# llrf_afe_fmc.net
KiCad netlist of a schematic drawn in Altium Designer
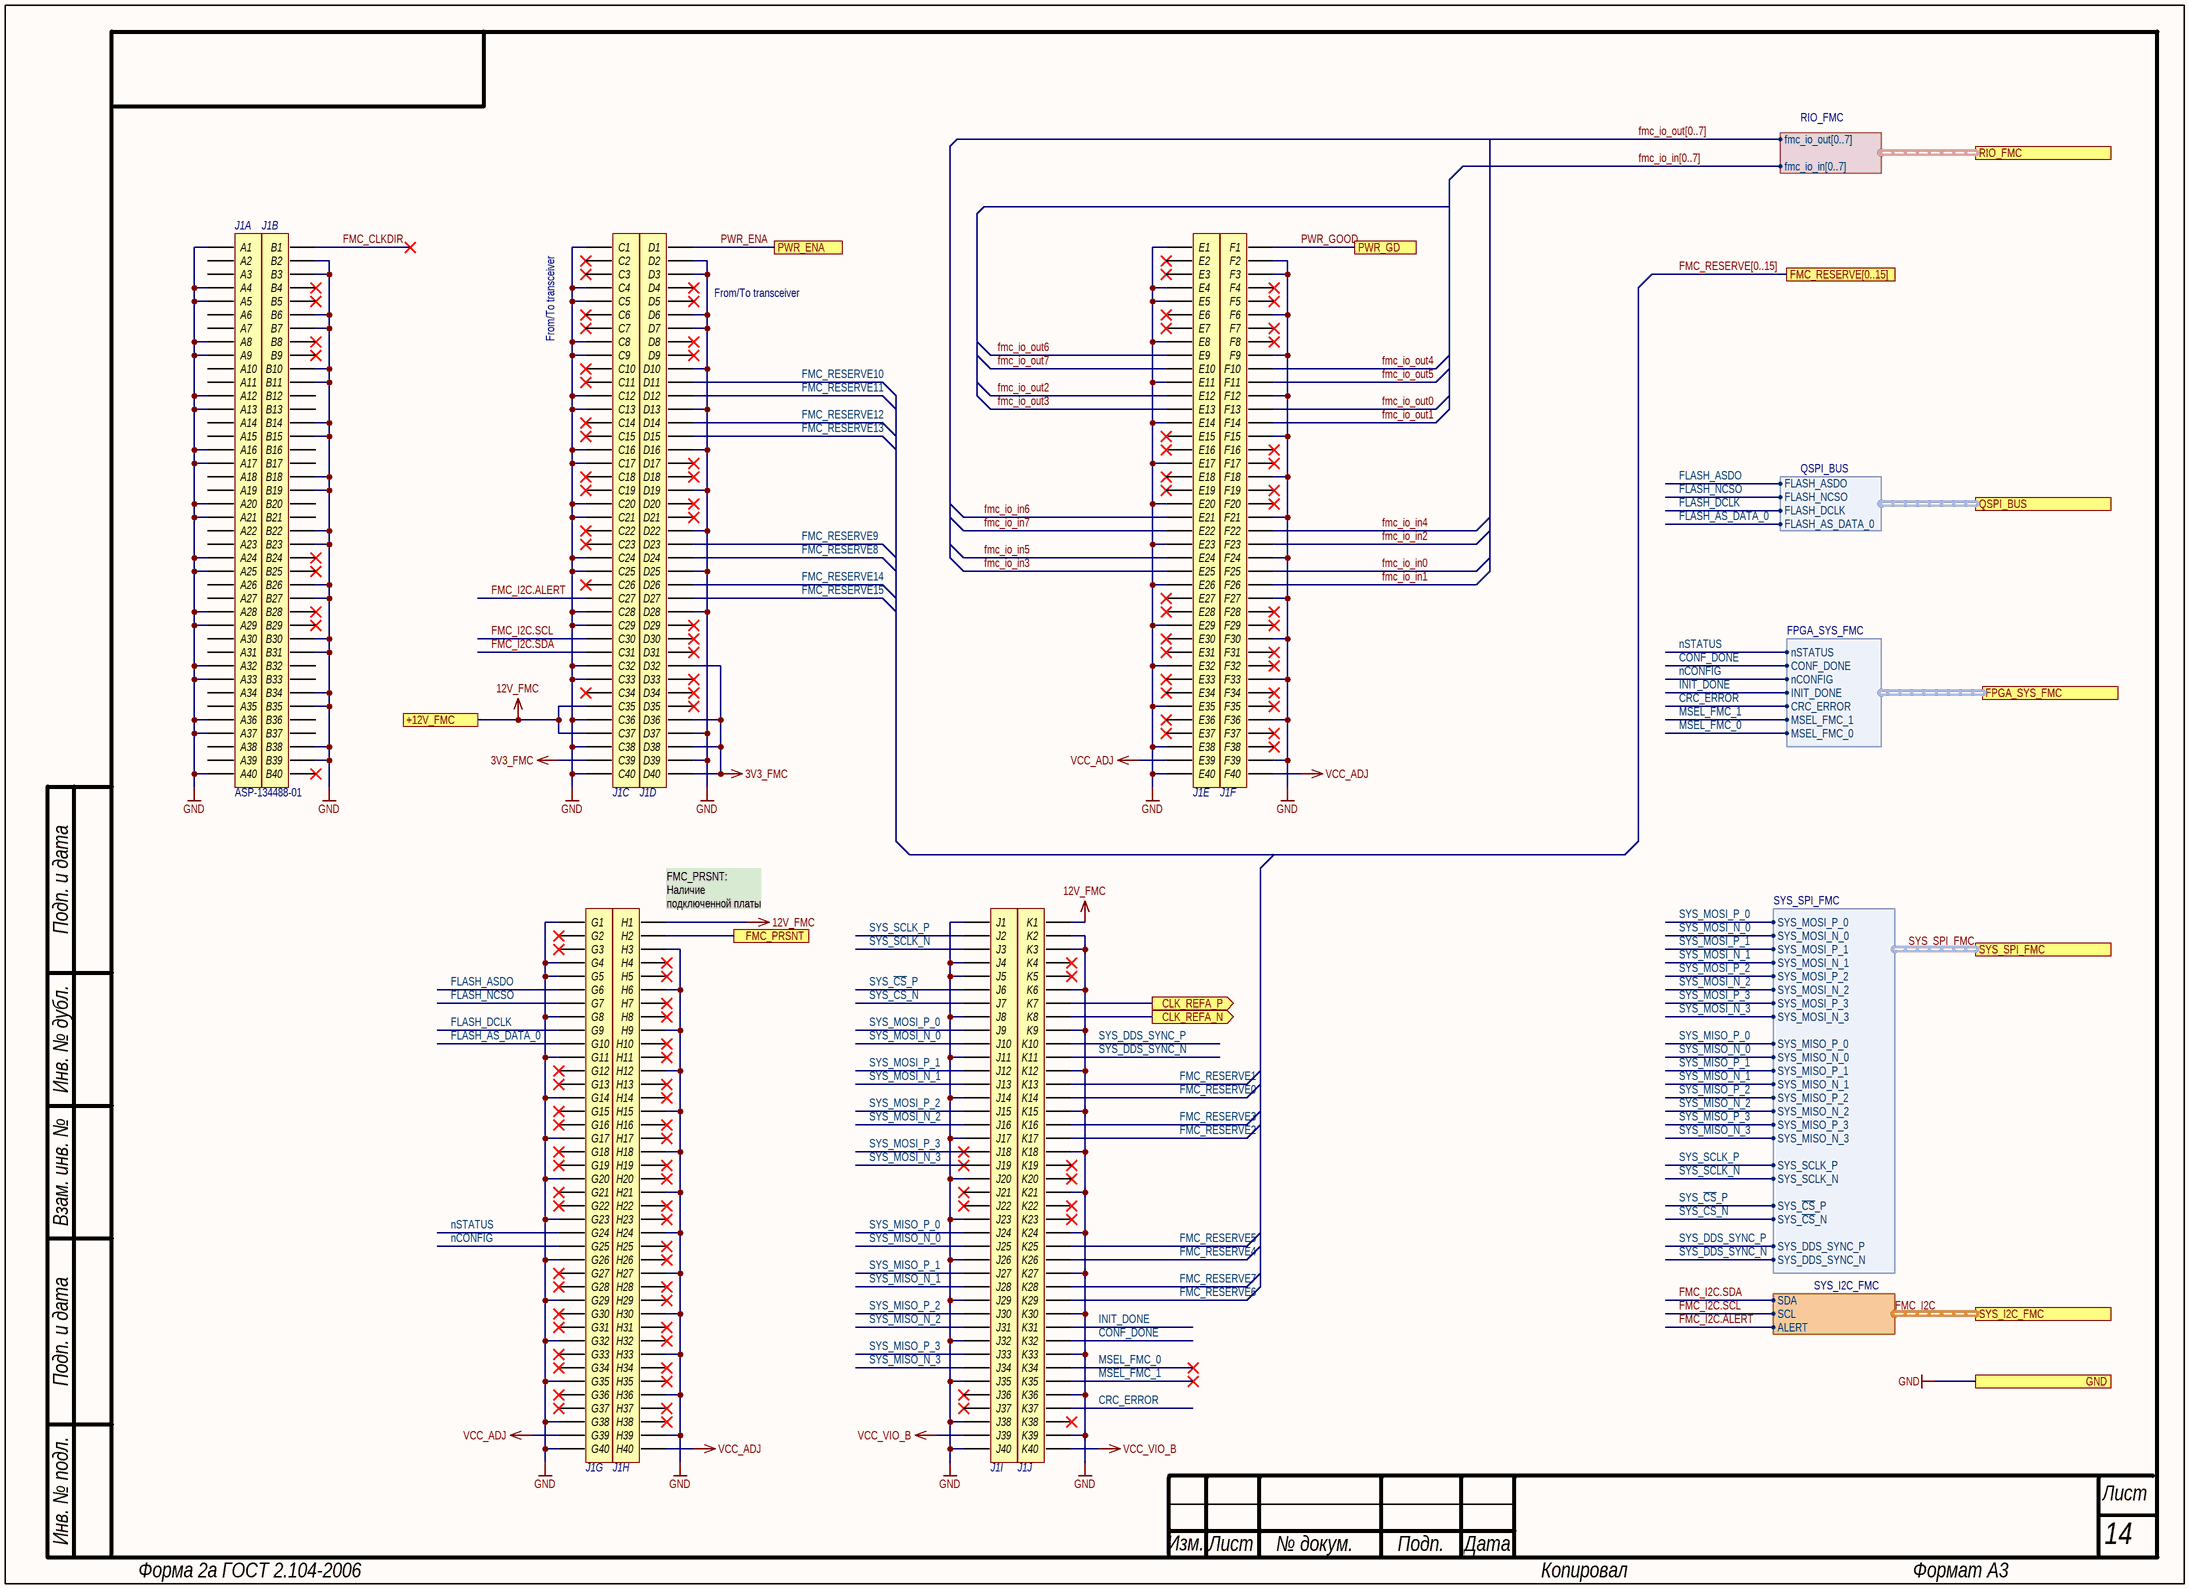
[diagram p0: llrf_afe_fmc.SchDoc]

(export (version "E")
  (design (tool "Eeschema 10.0.6"))
  (components
    (comp (ref "J1")
      (value "ASP-134488-01")
      (footprint "ASP-134488-01")
      (description "Socket Array Assembly, Surface Mount, 0.050\" Pitch, 400 Pins")
      (fields
        (field (name "MANUFACTURER") "SAMTEC")
        (field (name "НАИМЕНОВАНИЕ") "ASP-134488-01")
        (field (name "CREATED") "March 24, 2015 - Wendy Xin")
      )
      (libsource (lib "Connector") (part "ASP-134488-01"))
    )
  )
  (nets
    (net (code "6") (name "/CLK_REFA_N") (class "Default")
      (node (ref "J1") (pin "K8") (pinfunction "K8_K8") (pintype "passive"))
    )
    (net (code "7") (name "/CLK_REFA_P") (class "Default")
      (node (ref "J1") (pin "K7") (pinfunction "K7_K7") (pintype "passive"))
    )
    (net (code "8") (name "/CONF_DONE") (class "Default")
      (node (ref "J1") (pin "K32") (pinfunction "K32_K32") (pintype "passive"))
    )
    (net (code "9") (name "/CRC_ERROR") (class "Default")
      (node (ref "J1") (pin "K37") (pinfunction "K37_K37") (pintype "passive"))
    )
    (net (code "10") (name "/FLASH_ASDO") (class "Default")
      (node (ref "J1") (pin "G6") (pinfunction "G6_G6") (pintype "passive"))
    )
    (net (code "11") (name "/FLASH_AS_DATA_0") (class "Default")
      (node (ref "J1") (pin "G10") (pinfunction "G10_G10") (pintype "passive"))
    )
    (net (code "12") (name "/FLASH_DCLK") (class "Default")
      (node (ref "J1") (pin "G9") (pinfunction "G9_G9") (pintype "passive"))
    )
    (net (code "13") (name "/FLASH_NCSO") (class "Default")
      (node (ref "J1") (pin "G7") (pinfunction "G7_G7") (pintype "passive"))
    )
    (net (code "14") (name "/FMC_CLKDIR") (class "Default")
      (node (ref "J1") (pin "B1") (pinfunction "B1_B1") (pintype "passive+no_connect"))
    )
    (net (code "15") (name "/FMC_I2C.ALERT") (class "Default")
      (node (ref "J1") (pin "C27") (pinfunction "C27_C27") (pintype "passive"))
    )
    (net (code "16") (name "/FMC_I2C.SCL") (class "Default")
      (node (ref "J1") (pin "C30") (pinfunction "C30_C30") (pintype "passive"))
    )
    (net (code "17") (name "/FMC_I2C.SDA") (class "Default")
      (node (ref "J1") (pin "C31") (pinfunction "C31_C31") (pintype "passive"))
    )
    (net (code "19") (name "/FMC_PRSNT") (class "Default")
      (node (ref "J1") (pin "H2") (pinfunction "H2_H2") (pintype "passive"))
    )
    (net (code "20") (name "/FMC_RESERVE0") (class "Default")
      (node (ref "J1") (pin "K14") (pinfunction "K14_K14") (pintype "passive"))
    )
    (net (code "21") (name "/FMC_RESERVE1") (class "Default")
      (node (ref "J1") (pin "K13") (pinfunction "K13_K13") (pintype "passive"))
    )
    (net (code "22") (name "/FMC_RESERVE2") (class "Default")
      (node (ref "J1") (pin "K17") (pinfunction "K17_K17") (pintype "passive"))
    )
    (net (code "23") (name "/FMC_RESERVE3") (class "Default")
      (node (ref "J1") (pin "K16") (pinfunction "K16_K16") (pintype "passive"))
    )
    (net (code "24") (name "/FMC_RESERVE4") (class "Default")
      (node (ref "J1") (pin "K26") (pinfunction "K26_K26") (pintype "passive"))
    )
    (net (code "25") (name "/FMC_RESERVE5") (class "Default")
      (node (ref "J1") (pin "K25") (pinfunction "K25_K25") (pintype "passive"))
    )
    (net (code "26") (name "/FMC_RESERVE6") (class "Default")
      (node (ref "J1") (pin "K29") (pinfunction "K29_K29") (pintype "passive"))
    )
    (net (code "27") (name "/FMC_RESERVE7") (class "Default")
      (node (ref "J1") (pin "K28") (pinfunction "K28_K28") (pintype "passive"))
    )
    (net (code "28") (name "/FMC_RESERVE8") (class "Default")
      (node (ref "J1") (pin "D24") (pinfunction "D24_D24") (pintype "passive"))
    )
    (net (code "29") (name "/FMC_RESERVE9") (class "Default")
      (node (ref "J1") (pin "D23") (pinfunction "D23_D23") (pintype "passive"))
    )
    (net (code "30") (name "/FMC_RESERVE10") (class "Default")
      (node (ref "J1") (pin "D11") (pinfunction "D11_D11") (pintype "passive"))
    )
    (net (code "31") (name "/FMC_RESERVE11") (class "Default")
      (node (ref "J1") (pin "D12") (pinfunction "D12_D12") (pintype "passive"))
    )
    (net (code "32") (name "/FMC_RESERVE12") (class "Default")
      (node (ref "J1") (pin "D14") (pinfunction "D14_D14") (pintype "passive"))
    )
    (net (code "33") (name "/FMC_RESERVE13") (class "Default")
      (node (ref "J1") (pin "D15") (pinfunction "D15_D15") (pintype "passive"))
    )
    (net (code "34") (name "/FMC_RESERVE14") (class "Default")
      (node (ref "J1") (pin "D26") (pinfunction "D26_D26") (pintype "passive"))
    )
    (net (code "35") (name "/FMC_RESERVE15") (class "Default")
      (node (ref "J1") (pin "D27") (pinfunction "D27_D27") (pintype "passive"))
    )
    (net (code "37") (name "/INIT_DONE") (class "Default")
      (node (ref "J1") (pin "K31") (pinfunction "K31_K31") (pintype "passive"))
    )
    (net (code "38") (name "/MSEL_FMC_0") (class "Default")
      (node (ref "J1") (pin "K34") (pinfunction "K34_K34") (pintype "passive"))
    )
    (net (code "39") (name "/MSEL_FMC_1") (class "Default")
      (node (ref "J1") (pin "K35") (pinfunction "K35_K35") (pintype "passive"))
    )
    (net (code "40") (name "/PWR_ENA") (class "Default")
      (node (ref "J1") (pin "D1") (pinfunction "D1_D1") (pintype "passive"))
    )
    (net (code "41") (name "/PWR_GOOD") (class "Default")
      (node (ref "J1") (pin "F1") (pinfunction "F1_F1") (pintype "passive"))
    )
    (net (code "43") (name "/SYS_DDS_SYNC_N") (class "Default")
      (node (ref "J1") (pin "K11") (pinfunction "K11_K11") (pintype "passive"))
    )
    (net (code "44") (name "/SYS_DDS_SYNC_P") (class "Default")
      (node (ref "J1") (pin "K10") (pinfunction "K10_K10") (pintype "passive"))
    )
    (net (code "45") (name "/SYS_MISO_N_0") (class "Default")
      (node (ref "J1") (pin "J25") (pinfunction "J25_J25") (pintype "passive"))
    )
    (net (code "46") (name "/SYS_MISO_N_1") (class "Default")
      (node (ref "J1") (pin "J28") (pinfunction "J28_J28") (pintype "passive"))
    )
    (net (code "47") (name "/SYS_MISO_N_2") (class "Default")
      (node (ref "J1") (pin "J31") (pinfunction "J31_J31") (pintype "passive"))
    )
    (net (code "48") (name "/SYS_MISO_N_3") (class "Default")
      (node (ref "J1") (pin "J34") (pinfunction "J34_J34") (pintype "passive"))
    )
    (net (code "49") (name "/SYS_MISO_P_0") (class "Default")
      (node (ref "J1") (pin "J24") (pinfunction "J24_J24") (pintype "passive"))
    )
    (net (code "50") (name "/SYS_MISO_P_1") (class "Default")
      (node (ref "J1") (pin "J27") (pinfunction "J27_J27") (pintype "passive"))
    )
    (net (code "51") (name "/SYS_MISO_P_2") (class "Default")
      (node (ref "J1") (pin "J30") (pinfunction "J30_J30") (pintype "passive"))
    )
    (net (code "52") (name "/SYS_MISO_P_3") (class "Default")
      (node (ref "J1") (pin "J33") (pinfunction "J33_J33") (pintype "passive"))
    )
    (net (code "53") (name "/SYS_MOSI_N_0") (class "Default")
      (node (ref "J1") (pin "J10") (pinfunction "J10_J10") (pintype "passive"))
    )
    (net (code "54") (name "/SYS_MOSI_N_1") (class "Default")
      (node (ref "J1") (pin "J13") (pinfunction "J13_J13") (pintype "passive"))
    )
    (net (code "55") (name "/SYS_MOSI_N_2") (class "Default")
      (node (ref "J1") (pin "J16") (pinfunction "J16_J16") (pintype "passive"))
    )
    (net (code "56") (name "/SYS_MOSI_N_3") (class "Default")
      (node (ref "J1") (pin "J19") (pinfunction "J19_J19") (pintype "passive"))
    )
    (net (code "57") (name "/SYS_MOSI_P_0") (class "Default")
      (node (ref "J1") (pin "J9") (pinfunction "J9_J9") (pintype "passive"))
    )
    (net (code "58") (name "/SYS_MOSI_P_1") (class "Default")
      (node (ref "J1") (pin "J12") (pinfunction "J12_J12") (pintype "passive"))
    )
    (net (code "59") (name "/SYS_MOSI_P_2") (class "Default")
      (node (ref "J1") (pin "J15") (pinfunction "J15_J15") (pintype "passive"))
    )
    (net (code "60") (name "/SYS_MOSI_P_3") (class "Default")
      (node (ref "J1") (pin "J18") (pinfunction "J18_J18") (pintype "passive"))
    )
    (net (code "61") (name "/SYS_SCLK_N") (class "Default")
      (node (ref "J1") (pin "J3") (pinfunction "J3_J3") (pintype "passive"))
    )
    (net (code "62") (name "/SYS_SCLK_P") (class "Default")
      (node (ref "J1") (pin "J2") (pinfunction "J2_J2") (pintype "passive"))
    )
    (net (code "64") (name "/SYS_~{CS}_N") (class "Default")
      (node (ref "J1") (pin "J7") (pinfunction "J7_J7") (pintype "passive"))
    )
    (net (code "65") (name "/SYS_~{CS}_P") (class "Default")
      (node (ref "J1") (pin "J6") (pinfunction "J6_J6") (pintype "passive"))
    )
    (net (code "66") (name "/fmc_io_in0") (class "Default")
      (node (ref "J1") (pin "F25") (pinfunction "F25_F25") (pintype "passive"))
    )
    (net (code "67") (name "/fmc_io_in1") (class "Default")
      (node (ref "J1") (pin "F26") (pinfunction "F26_F26") (pintype "passive"))
    )
    (net (code "68") (name "/fmc_io_in2") (class "Default")
      (node (ref "J1") (pin "F23") (pinfunction "F23_F23") (pintype "passive"))
    )
    (net (code "69") (name "/fmc_io_in3") (class "Default")
      (node (ref "J1") (pin "E25") (pinfunction "E25_E25") (pintype "passive"))
    )
    (net (code "70") (name "/fmc_io_in4") (class "Default")
      (node (ref "J1") (pin "F22") (pinfunction "F22_F22") (pintype "passive"))
    )
    (net (code "71") (name "/fmc_io_in5") (class "Default")
      (node (ref "J1") (pin "E24") (pinfunction "E24_E24") (pintype "passive"))
    )
    (net (code "72") (name "/fmc_io_in6") (class "Default")
      (node (ref "J1") (pin "E21") (pinfunction "E21_E21") (pintype "passive"))
    )
    (net (code "73") (name "/fmc_io_in7") (class "Default")
      (node (ref "J1") (pin "E22") (pinfunction "E22_E22") (pintype "passive"))
    )
    (net (code "75") (name "/fmc_io_out0") (class "Default")
      (node (ref "J1") (pin "F13") (pinfunction "F13_F13") (pintype "passive"))
    )
    (net (code "76") (name "/fmc_io_out1") (class "Default")
      (node (ref "J1") (pin "F14") (pinfunction "F14_F14") (pintype "passive"))
    )
    (net (code "77") (name "/fmc_io_out2") (class "Default")
      (node (ref "J1") (pin "E12") (pinfunction "E12_E12") (pintype "passive"))
    )
    (net (code "78") (name "/fmc_io_out3") (class "Default")
      (node (ref "J1") (pin "E13") (pinfunction "E13_E13") (pintype "passive"))
    )
    (net (code "79") (name "/fmc_io_out4") (class "Default")
      (node (ref "J1") (pin "F10") (pinfunction "F10_F10") (pintype "passive"))
    )
    (net (code "80") (name "/fmc_io_out5") (class "Default")
      (node (ref "J1") (pin "F11") (pinfunction "F11_F11") (pintype "passive"))
    )
    (net (code "81") (name "/fmc_io_out6") (class "Default")
      (node (ref "J1") (pin "E9") (pinfunction "E9_E9") (pintype "passive"))
    )
    (net (code "82") (name "/fmc_io_out7") (class "Default")
      (node (ref "J1") (pin "E10") (pinfunction "E10_E10") (pintype "passive"))
    )
    (net (code "83") (name "/nCONFIG") (class "Default")
      (node (ref "J1") (pin "G25") (pinfunction "G25_G25") (pintype "passive"))
    )
    (net (code "84") (name "/nSTATUS") (class "Default")
      (node (ref "J1") (pin "G24") (pinfunction "G24_G24") (pintype "passive"))
    )
    (net (code "88") (name "3V3_FMC") (class "Default")
      (node (ref "J1") (pin "C39") (pinfunction "C39_C39") (pintype "passive"))
      (node (ref "J1") (pin "D32") (pinfunction "D32_D32") (pintype "passive"))
      (node (ref "J1") (pin "D36") (pinfunction "D36_D36") (pintype "passive"))
      (node (ref "J1") (pin "D38") (pinfunction "D38_D38") (pintype "passive"))
      (node (ref "J1") (pin "D40") (pinfunction "D40_D40") (pintype "passive"))
    )
    (net (code "89") (name "12V_FMC") (class "Default")
      (node (ref "J1") (pin "C35") (pinfunction "C35_C35") (pintype "passive"))
      (node (ref "J1") (pin "C37") (pinfunction "C37_C37") (pintype "passive"))
      (node (ref "J1") (pin "H1") (pinfunction "H1_H1") (pintype "passive"))
      (node (ref "J1") (pin "K1") (pinfunction "K1_K1") (pintype "passive"))
    )
    (net (code "90") (name "GND") (class "Default")
      (node (ref "J1") (pin "A1") (pinfunction "A1_A1") (pintype "passive"))
      (node (ref "J1") (pin "A12") (pinfunction "A12_A12") (pintype "passive"))
      (node (ref "J1") (pin "A13") (pinfunction "A13_A13") (pintype "passive"))
      (node (ref "J1") (pin "A16") (pinfunction "A16_A16") (pintype "passive"))
      (node (ref "J1") (pin "A17") (pinfunction "A17_A17") (pintype "passive"))
      (node (ref "J1") (pin "A20") (pinfunction "A20_A20") (pintype "passive"))
      (node (ref "J1") (pin "A21") (pinfunction "A21_A21") (pintype "passive"))
      (node (ref "J1") (pin "A24") (pinfunction "A24_A24") (pintype "passive"))
      (node (ref "J1") (pin "A25") (pinfunction "A25_A25") (pintype "passive"))
      (node (ref "J1") (pin "A28") (pinfunction "A28_A28") (pintype "passive"))
      (node (ref "J1") (pin "A29") (pinfunction "A29_A29") (pintype "passive"))
      (node (ref "J1") (pin "A32") (pinfunction "A32_A32") (pintype "passive"))
      (node (ref "J1") (pin "A33") (pinfunction "A33_A33") (pintype "passive"))
      (node (ref "J1") (pin "A36") (pinfunction "A36_A36") (pintype "passive"))
      (node (ref "J1") (pin "A37") (pinfunction "A37_A37") (pintype "passive"))
      (node (ref "J1") (pin "A4") (pinfunction "A4_A4") (pintype "passive"))
      (node (ref "J1") (pin "A40") (pinfunction "A40_A40") (pintype "passive"))
      (node (ref "J1") (pin "A5") (pinfunction "A5_A5") (pintype "passive"))
      (node (ref "J1") (pin "A8") (pinfunction "A8_A8") (pintype "passive"))
      (node (ref "J1") (pin "A9") (pinfunction "A9_A9") (pintype "passive"))
      (node (ref "J1") (pin "B10") (pinfunction "B10_B10") (pintype "passive"))
      (node (ref "J1") (pin "B11") (pinfunction "B11_B11") (pintype "passive"))
      (node (ref "J1") (pin "B14") (pinfunction "B14_B14") (pintype "passive"))
      (node (ref "J1") (pin "B15") (pinfunction "B15_B15") (pintype "passive"))
      (node (ref "J1") (pin "B18") (pinfunction "B18_B18") (pintype "passive"))
      (node (ref "J1") (pin "B19") (pinfunction "B19_B19") (pintype "passive"))
      (node (ref "J1") (pin "B2") (pinfunction "B2_B2") (pintype "passive"))
      (node (ref "J1") (pin "B22") (pinfunction "B22_B22") (pintype "passive"))
      (node (ref "J1") (pin "B23") (pinfunction "B23_B23") (pintype "passive"))
      (node (ref "J1") (pin "B26") (pinfunction "B26_B26") (pintype "passive"))
      (node (ref "J1") (pin "B27") (pinfunction "B27_B27") (pintype "passive"))
      (node (ref "J1") (pin "B3") (pinfunction "B3_B3") (pintype "passive"))
      (node (ref "J1") (pin "B30") (pinfunction "B30_B30") (pintype "passive"))
      (node (ref "J1") (pin "B31") (pinfunction "B31_B31") (pintype "passive"))
      (node (ref "J1") (pin "B34") (pinfunction "B34_B34") (pintype "passive"))
      (node (ref "J1") (pin "B35") (pinfunction "B35_B35") (pintype "passive"))
      (node (ref "J1") (pin "B38") (pinfunction "B38_B38") (pintype "passive"))
      (node (ref "J1") (pin "B39") (pinfunction "B39_B39") (pintype "passive"))
      (node (ref "J1") (pin "B6") (pinfunction "B6_B6") (pintype "passive"))
      (node (ref "J1") (pin "B7") (pinfunction "B7_B7") (pintype "passive"))
      (node (ref "J1") (pin "C1") (pinfunction "C1_C1") (pintype "passive"))
      (node (ref "J1") (pin "C12") (pinfunction "C12_C12") (pintype "passive"))
      (node (ref "J1") (pin "C13") (pinfunction "C13_C13") (pintype "passive"))
      (node (ref "J1") (pin "C16") (pinfunction "C16_C16") (pintype "passive"))
      (node (ref "J1") (pin "C17") (pinfunction "C17_C17") (pintype "passive"))
      (node (ref "J1") (pin "C20") (pinfunction "C20_C20") (pintype "passive"))
      (node (ref "J1") (pin "C21") (pinfunction "C21_C21") (pintype "passive"))
      (node (ref "J1") (pin "C24") (pinfunction "C24_C24") (pintype "passive"))
      (node (ref "J1") (pin "C25") (pinfunction "C25_C25") (pintype "passive"))
      (node (ref "J1") (pin "C28") (pinfunction "C28_C28") (pintype "passive"))
      (node (ref "J1") (pin "C29") (pinfunction "C29_C29") (pintype "passive"))
      (node (ref "J1") (pin "C32") (pinfunction "C32_C32") (pintype "passive"))
      (node (ref "J1") (pin "C33") (pinfunction "C33_C33") (pintype "passive"))
      (node (ref "J1") (pin "C36") (pinfunction "C36_C36") (pintype "passive"))
      (node (ref "J1") (pin "C38") (pinfunction "C38_C38") (pintype "passive"))
      (node (ref "J1") (pin "C4") (pinfunction "C4_C4") (pintype "passive"))
      (node (ref "J1") (pin "C40") (pinfunction "C40_C40") (pintype "passive"))
      (node (ref "J1") (pin "C5") (pinfunction "C5_C5") (pintype "passive"))
      (node (ref "J1") (pin "C8") (pinfunction "C8_C8") (pintype "passive"))
      (node (ref "J1") (pin "C9") (pinfunction "C9_C9") (pintype "passive"))
      (node (ref "J1") (pin "D10") (pinfunction "D10_D10") (pintype "passive"))
      (node (ref "J1") (pin "D13") (pinfunction "D13_D13") (pintype "passive"))
      (node (ref "J1") (pin "D16") (pinfunction "D16_D16") (pintype "passive"))
      (node (ref "J1") (pin "D19") (pinfunction "D19_D19") (pintype "passive"))
      (node (ref "J1") (pin "D2") (pinfunction "D2_D2") (pintype "passive"))
      (node (ref "J1") (pin "D22") (pinfunction "D22_D22") (pintype "passive"))
      (node (ref "J1") (pin "D25") (pinfunction "D25_D25") (pintype "passive"))
      (node (ref "J1") (pin "D28") (pinfunction "D28_D28") (pintype "passive"))
      (node (ref "J1") (pin "D3") (pinfunction "D3_D3") (pintype "passive"))
      (node (ref "J1") (pin "D37") (pinfunction "D37_D37") (pintype "passive"))
      (node (ref "J1") (pin "D39") (pinfunction "D39_D39") (pintype "passive"))
      (node (ref "J1") (pin "D6") (pinfunction "D6_D6") (pintype "passive"))
      (node (ref "J1") (pin "D7") (pinfunction "D7_D7") (pintype "passive"))
      (node (ref "J1") (pin "E1") (pinfunction "E1_E1") (pintype "passive"))
      (node (ref "J1") (pin "E11") (pinfunction "E11_E11") (pintype "passive"))
      (node (ref "J1") (pin "E14") (pinfunction "E14_E14") (pintype "passive"))
      (node (ref "J1") (pin "E17") (pinfunction "E17_E17") (pintype "passive"))
      (node (ref "J1") (pin "E20") (pinfunction "E20_E20") (pintype "passive"))
      (node (ref "J1") (pin "E23") (pinfunction "E23_E23") (pintype "passive"))
      (node (ref "J1") (pin "E26") (pinfunction "E26_E26") (pintype "passive"))
      (node (ref "J1") (pin "E29") (pinfunction "E29_E29") (pintype "passive"))
      (node (ref "J1") (pin "E32") (pinfunction "E32_E32") (pintype "passive"))
      (node (ref "J1") (pin "E35") (pinfunction "E35_E35") (pintype "passive"))
      (node (ref "J1") (pin "E38") (pinfunction "E38_E38") (pintype "passive"))
      (node (ref "J1") (pin "E4") (pinfunction "E4_E4") (pintype "passive"))
      (node (ref "J1") (pin "E40") (pinfunction "E40_E40") (pintype "passive"))
      (node (ref "J1") (pin "E5") (pinfunction "E5_E5") (pintype "passive"))
      (node (ref "J1") (pin "E8") (pinfunction "E8_E8") (pintype "passive"))
      (node (ref "J1") (pin "F12") (pinfunction "F12_F12") (pintype "passive"))
      (node (ref "J1") (pin "F15") (pinfunction "F15_F15") (pintype "passive"))
      (node (ref "J1") (pin "F18") (pinfunction "F18_F18") (pintype "passive"))
      (node (ref "J1") (pin "F2") (pinfunction "F2_F2") (pintype "passive"))
      (node (ref "J1") (pin "F21") (pinfunction "F21_F21") (pintype "passive"))
      (node (ref "J1") (pin "F24") (pinfunction "F24_F24") (pintype "passive"))
      (node (ref "J1") (pin "F27") (pinfunction "F27_F27") (pintype "passive"))
      (node (ref "J1") (pin "F3") (pinfunction "F3_F3") (pintype "passive"))
      (node (ref "J1") (pin "F30") (pinfunction "F30_F30") (pintype "passive"))
      (node (ref "J1") (pin "F33") (pinfunction "F33_F33") (pintype "passive"))
      (node (ref "J1") (pin "F36") (pinfunction "F36_F36") (pintype "passive"))
      (node (ref "J1") (pin "F39") (pinfunction "F39_F39") (pintype "passive"))
      (node (ref "J1") (pin "F6") (pinfunction "F6_F6") (pintype "passive"))
      (node (ref "J1") (pin "F9") (pinfunction "F9_F9") (pintype "passive"))
      (node (ref "J1") (pin "G1") (pinfunction "G1_G1") (pintype "passive"))
      (node (ref "J1") (pin "G11") (pinfunction "G11_G11") (pintype "passive"))
      (node (ref "J1") (pin "G14") (pinfunction "G14_G14") (pintype "passive"))
      (node (ref "J1") (pin "G17") (pinfunction "G17_G17") (pintype "passive"))
      (node (ref "J1") (pin "G20") (pinfunction "G20_G20") (pintype "passive"))
      (node (ref "J1") (pin "G23") (pinfunction "G23_G23") (pintype "passive"))
      (node (ref "J1") (pin "G26") (pinfunction "G26_G26") (pintype "passive"))
      (node (ref "J1") (pin "G29") (pinfunction "G29_G29") (pintype "passive"))
      (node (ref "J1") (pin "G32") (pinfunction "G32_G32") (pintype "passive"))
      (node (ref "J1") (pin "G35") (pinfunction "G35_G35") (pintype "passive"))
      (node (ref "J1") (pin "G38") (pinfunction "G38_G38") (pintype "passive"))
      (node (ref "J1") (pin "G4") (pinfunction "G4_G4") (pintype "passive"))
      (node (ref "J1") (pin "G40") (pinfunction "G40_G40") (pintype "passive"))
      (node (ref "J1") (pin "G5") (pinfunction "G5_G5") (pintype "passive"))
      (node (ref "J1") (pin "G8") (pinfunction "G8_G8") (pintype "passive"))
      (node (ref "J1") (pin "H12") (pinfunction "H12_H12") (pintype "passive"))
      (node (ref "J1") (pin "H15") (pinfunction "H15_H15") (pintype "passive"))
      (node (ref "J1") (pin "H18") (pinfunction "H18_H18") (pintype "passive"))
      (node (ref "J1") (pin "H21") (pinfunction "H21_H21") (pintype "passive"))
      (node (ref "J1") (pin "H24") (pinfunction "H24_H24") (pintype "passive"))
      (node (ref "J1") (pin "H27") (pinfunction "H27_H27") (pintype "passive"))
      (node (ref "J1") (pin "H3") (pinfunction "H3_H3") (pintype "passive"))
      (node (ref "J1") (pin "H30") (pinfunction "H30_H30") (pintype "passive"))
      (node (ref "J1") (pin "H33") (pinfunction "H33_H33") (pintype "passive"))
      (node (ref "J1") (pin "H36") (pinfunction "H36_H36") (pintype "passive"))
      (node (ref "J1") (pin "H39") (pinfunction "H39_H39") (pintype "passive"))
      (node (ref "J1") (pin "H6") (pinfunction "H6_H6") (pintype "passive"))
      (node (ref "J1") (pin "H9") (pinfunction "H9_H9") (pintype "passive"))
      (node (ref "J1") (pin "J1") (pinfunction "J1_J1") (pintype "passive"))
      (node (ref "J1") (pin "J11") (pinfunction "J11_J11") (pintype "passive"))
      (node (ref "J1") (pin "J14") (pinfunction "J14_J14") (pintype "passive"))
      (node (ref "J1") (pin "J17") (pinfunction "J17_J17") (pintype "passive"))
      (node (ref "J1") (pin "J20") (pinfunction "J20_J20") (pintype "passive"))
      (node (ref "J1") (pin "J23") (pinfunction "J23_J23") (pintype "passive"))
      (node (ref "J1") (pin "J26") (pinfunction "J26_J26") (pintype "passive"))
      (node (ref "J1") (pin "J29") (pinfunction "J29_J29") (pintype "passive"))
      (node (ref "J1") (pin "J32") (pinfunction "J32_J32") (pintype "passive"))
      (node (ref "J1") (pin "J35") (pinfunction "J35_J35") (pintype "passive"))
      (node (ref "J1") (pin "J38") (pinfunction "J38_J38") (pintype "passive"))
      (node (ref "J1") (pin "J4") (pinfunction "J4_J4") (pintype "passive"))
      (node (ref "J1") (pin "J40") (pinfunction "J40_J40") (pintype "passive"))
      (node (ref "J1") (pin "J5") (pinfunction "J5_J5") (pintype "passive"))
      (node (ref "J1") (pin "J8") (pinfunction "J8_J8") (pintype "passive"))
      (node (ref "J1") (pin "K12") (pinfunction "K12_K12") (pintype "passive"))
      (node (ref "J1") (pin "K15") (pinfunction "K15_K15") (pintype "passive"))
      (node (ref "J1") (pin "K18") (pinfunction "K18_K18") (pintype "passive"))
      (node (ref "J1") (pin "K2") (pinfunction "K2_K2") (pintype "passive"))
      (node (ref "J1") (pin "K21") (pinfunction "K21_K21") (pintype "passive"))
      (node (ref "J1") (pin "K24") (pinfunction "K24_K24") (pintype "passive"))
      (node (ref "J1") (pin "K27") (pinfunction "K27_K27") (pintype "passive"))
      (node (ref "J1") (pin "K3") (pinfunction "K3_K3") (pintype "passive"))
      (node (ref "J1") (pin "K30") (pinfunction "K30_K30") (pintype "passive"))
      (node (ref "J1") (pin "K33") (pinfunction "K33_K33") (pintype "passive"))
      (node (ref "J1") (pin "K36") (pinfunction "K36_K36") (pintype "passive"))
      (node (ref "J1") (pin "K39") (pinfunction "K39_K39") (pintype "passive"))
      (node (ref "J1") (pin "K6") (pinfunction "K6_K6") (pintype "passive"))
      (node (ref "J1") (pin "K9") (pinfunction "K9_K9") (pintype "passive"))
    )
    (net (code "91") (name "VCC_ADJ") (class "Default")
      (node (ref "J1") (pin "E39") (pinfunction "E39_E39") (pintype "passive"))
      (node (ref "J1") (pin "F40") (pinfunction "F40_F40") (pintype "passive"))
      (node (ref "J1") (pin "G39") (pinfunction "G39_G39") (pintype "passive"))
      (node (ref "J1") (pin "H40") (pinfunction "H40_H40") (pintype "passive"))
    )
    (net (code "92") (name "VCC_VIO_B") (class "Default")
      (node (ref "J1") (pin "J39") (pinfunction "J39_J39") (pintype "passive"))
      (node (ref "J1") (pin "K40") (pinfunction "K40_K40") (pintype "passive"))
    )
    (net (code "93") (name "unconnected-(J1-PadA2)") (class "Default")
      (node (ref "J1") (pin "A2") (pinfunction "A2_A2") (pintype "passive"))
    )
    (net (code "94") (name "unconnected-(J1-PadA3)") (class "Default")
      (node (ref "J1") (pin "A3") (pinfunction "A3_A3") (pintype "passive"))
    )
    (net (code "95") (name "unconnected-(J1-PadA6)") (class "Default")
      (node (ref "J1") (pin "A6") (pinfunction "A6_A6") (pintype "passive"))
    )
    (net (code "96") (name "unconnected-(J1-PadA7)") (class "Default")
      (node (ref "J1") (pin "A7") (pinfunction "A7_A7") (pintype "passive"))
    )
    (net (code "97") (name "unconnected-(J1-PadA10)") (class "Default")
      (node (ref "J1") (pin "A10") (pinfunction "A10_A10") (pintype "passive"))
    )
    (net (code "98") (name "unconnected-(J1-PadA11)") (class "Default")
      (node (ref "J1") (pin "A11") (pinfunction "A11_A11") (pintype "passive"))
    )
    (net (code "99") (name "unconnected-(J1-PadA14)") (class "Default")
      (node (ref "J1") (pin "A14") (pinfunction "A14_A14") (pintype "passive"))
    )
    (net (code "100") (name "unconnected-(J1-PadA15)") (class "Default")
      (node (ref "J1") (pin "A15") (pinfunction "A15_A15") (pintype "passive"))
    )
    (net (code "101") (name "unconnected-(J1-PadA18)") (class "Default")
      (node (ref "J1") (pin "A18") (pinfunction "A18_A18") (pintype "passive"))
    )
    (net (code "102") (name "unconnected-(J1-PadA19)") (class "Default")
      (node (ref "J1") (pin "A19") (pinfunction "A19_A19") (pintype "passive"))
    )
    (net (code "103") (name "unconnected-(J1-PadA22)") (class "Default")
      (node (ref "J1") (pin "A22") (pinfunction "A22_A22") (pintype "passive"))
    )
    (net (code "104") (name "unconnected-(J1-PadA23)") (class "Default")
      (node (ref "J1") (pin "A23") (pinfunction "A23_A23") (pintype "passive"))
    )
    (net (code "105") (name "unconnected-(J1-PadA26)") (class "Default")
      (node (ref "J1") (pin "A26") (pinfunction "A26_A26") (pintype "passive"))
    )
    (net (code "106") (name "unconnected-(J1-PadA27)") (class "Default")
      (node (ref "J1") (pin "A27") (pinfunction "A27_A27") (pintype "passive"))
    )
    (net (code "107") (name "unconnected-(J1-PadA30)") (class "Default")
      (node (ref "J1") (pin "A30") (pinfunction "A30_A30") (pintype "passive"))
    )
    (net (code "108") (name "unconnected-(J1-PadA31)") (class "Default")
      (node (ref "J1") (pin "A31") (pinfunction "A31_A31") (pintype "passive"))
    )
    (net (code "109") (name "unconnected-(J1-PadA34)") (class "Default")
      (node (ref "J1") (pin "A34") (pinfunction "A34_A34") (pintype "passive"))
    )
    (net (code "110") (name "unconnected-(J1-PadA35)") (class "Default")
      (node (ref "J1") (pin "A35") (pinfunction "A35_A35") (pintype "passive"))
    )
    (net (code "111") (name "unconnected-(J1-PadA38)") (class "Default")
      (node (ref "J1") (pin "A38") (pinfunction "A38_A38") (pintype "passive"))
    )
    (net (code "112") (name "unconnected-(J1-PadA39)") (class "Default")
      (node (ref "J1") (pin "A39") (pinfunction "A39_A39") (pintype "passive"))
    )
    (net (code "113") (name "unconnected-(J1-PadB4)") (class "Default")
      (node (ref "J1") (pin "B4") (pinfunction "B4_B4") (pintype "passive+no_connect"))
    )
    (net (code "114") (name "unconnected-(J1-PadB5)") (class "Default")
      (node (ref "J1") (pin "B5") (pinfunction "B5_B5") (pintype "passive+no_connect"))
    )
    (net (code "115") (name "unconnected-(J1-PadB8)") (class "Default")
      (node (ref "J1") (pin "B8") (pinfunction "B8_B8") (pintype "passive+no_connect"))
    )
    (net (code "116") (name "unconnected-(J1-PadB9)") (class "Default")
      (node (ref "J1") (pin "B9") (pinfunction "B9_B9") (pintype "passive+no_connect"))
    )
    (net (code "117") (name "unconnected-(J1-PadB12)") (class "Default")
      (node (ref "J1") (pin "B12") (pinfunction "B12_B12") (pintype "passive"))
    )
    (net (code "118") (name "unconnected-(J1-PadB13)") (class "Default")
      (node (ref "J1") (pin "B13") (pinfunction "B13_B13") (pintype "passive"))
    )
    (net (code "119") (name "unconnected-(J1-PadB16)") (class "Default")
      (node (ref "J1") (pin "B16") (pinfunction "B16_B16") (pintype "passive"))
    )
    (net (code "120") (name "unconnected-(J1-PadB17)") (class "Default")
      (node (ref "J1") (pin "B17") (pinfunction "B17_B17") (pintype "passive"))
    )
    (net (code "121") (name "unconnected-(J1-PadB20)") (class "Default")
      (node (ref "J1") (pin "B20") (pinfunction "B20_B20") (pintype "passive"))
    )
    (net (code "122") (name "unconnected-(J1-PadB21)") (class "Default")
      (node (ref "J1") (pin "B21") (pinfunction "B21_B21") (pintype "passive"))
    )
    (net (code "123") (name "unconnected-(J1-PadB24)") (class "Default")
      (node (ref "J1") (pin "B24") (pinfunction "B24_B24") (pintype "passive+no_connect"))
    )
    (net (code "124") (name "unconnected-(J1-PadB25)") (class "Default")
      (node (ref "J1") (pin "B25") (pinfunction "B25_B25") (pintype "passive+no_connect"))
    )
    (net (code "125") (name "unconnected-(J1-PadB28)") (class "Default")
      (node (ref "J1") (pin "B28") (pinfunction "B28_B28") (pintype "passive+no_connect"))
    )
    (net (code "126") (name "unconnected-(J1-PadB29)") (class "Default")
      (node (ref "J1") (pin "B29") (pinfunction "B29_B29") (pintype "passive+no_connect"))
    )
    (net (code "127") (name "unconnected-(J1-PadB32)") (class "Default")
      (node (ref "J1") (pin "B32") (pinfunction "B32_B32") (pintype "passive"))
    )
    (net (code "128") (name "unconnected-(J1-PadB33)") (class "Default")
      (node (ref "J1") (pin "B33") (pinfunction "B33_B33") (pintype "passive"))
    )
    (net (code "129") (name "unconnected-(J1-PadB36)") (class "Default")
      (node (ref "J1") (pin "B36") (pinfunction "B36_B36") (pintype "passive"))
    )
    (net (code "130") (name "unconnected-(J1-PadB37)") (class "Default")
      (node (ref "J1") (pin "B37") (pinfunction "B37_B37") (pintype "passive"))
    )
    (net (code "131") (name "unconnected-(J1-PadB40)") (class "Default")
      (node (ref "J1") (pin "B40") (pinfunction "B40_B40") (pintype "passive+no_connect"))
    )
    (net (code "132") (name "unconnected-(J1-PadC2)") (class "Default")
      (node (ref "J1") (pin "C2") (pinfunction "C2_C2") (pintype "passive+no_connect"))
    )
    (net (code "133") (name "unconnected-(J1-PadC3)") (class "Default")
      (node (ref "J1") (pin "C3") (pinfunction "C3_C3") (pintype "passive+no_connect"))
    )
    (net (code "134") (name "unconnected-(J1-PadC6)") (class "Default")
      (node (ref "J1") (pin "C6") (pinfunction "C6_C6") (pintype "passive+no_connect"))
    )
    (net (code "135") (name "unconnected-(J1-PadC7)") (class "Default")
      (node (ref "J1") (pin "C7") (pinfunction "C7_C7") (pintype "passive+no_connect"))
    )
    (net (code "136") (name "unconnected-(J1-PadC10)") (class "Default")
      (node (ref "J1") (pin "C10") (pinfunction "C10_C10") (pintype "passive+no_connect"))
    )
    (net (code "137") (name "unconnected-(J1-PadC11)") (class "Default")
      (node (ref "J1") (pin "C11") (pinfunction "C11_C11") (pintype "passive+no_connect"))
    )
    (net (code "138") (name "unconnected-(J1-PadC14)") (class "Default")
      (node (ref "J1") (pin "C14") (pinfunction "C14_C14") (pintype "passive+no_connect"))
    )
    (net (code "139") (name "unconnected-(J1-PadC15)") (class "Default")
      (node (ref "J1") (pin "C15") (pinfunction "C15_C15") (pintype "passive+no_connect"))
    )
    (net (code "140") (name "unconnected-(J1-PadC18)") (class "Default")
      (node (ref "J1") (pin "C18") (pinfunction "C18_C18") (pintype "passive+no_connect"))
    )
    (net (code "141") (name "unconnected-(J1-PadC19)") (class "Default")
      (node (ref "J1") (pin "C19") (pinfunction "C19_C19") (pintype "passive+no_connect"))
    )
    (net (code "142") (name "unconnected-(J1-PadC22)") (class "Default")
      (node (ref "J1") (pin "C22") (pinfunction "C22_C22") (pintype "passive+no_connect"))
    )
    (net (code "143") (name "unconnected-(J1-PadC23)") (class "Default")
      (node (ref "J1") (pin "C23") (pinfunction "C23_C23") (pintype "passive+no_connect"))
    )
    (net (code "144") (name "unconnected-(J1-PadC26)") (class "Default")
      (node (ref "J1") (pin "C26") (pinfunction "C26_C26") (pintype "passive+no_connect"))
    )
    (net (code "145") (name "unconnected-(J1-PadC34)") (class "Default")
      (node (ref "J1") (pin "C34") (pinfunction "C34_C34") (pintype "passive+no_connect"))
    )
    (net (code "146") (name "unconnected-(J1-PadD4)") (class "Default")
      (node (ref "J1") (pin "D4") (pinfunction "D4_D4") (pintype "passive+no_connect"))
    )
    (net (code "147") (name "unconnected-(J1-PadD5)") (class "Default")
      (node (ref "J1") (pin "D5") (pinfunction "D5_D5") (pintype "passive+no_connect"))
    )
    (net (code "148") (name "unconnected-(J1-PadD8)") (class "Default")
      (node (ref "J1") (pin "D8") (pinfunction "D8_D8") (pintype "passive+no_connect"))
    )
    (net (code "149") (name "unconnected-(J1-PadD9)") (class "Default")
      (node (ref "J1") (pin "D9") (pinfunction "D9_D9") (pintype "passive+no_connect"))
    )
    (net (code "150") (name "unconnected-(J1-PadD17)") (class "Default")
      (node (ref "J1") (pin "D17") (pinfunction "D17_D17") (pintype "passive+no_connect"))
    )
    (net (code "151") (name "unconnected-(J1-PadD18)") (class "Default")
      (node (ref "J1") (pin "D18") (pinfunction "D18_D18") (pintype "passive+no_connect"))
    )
    (net (code "152") (name "unconnected-(J1-PadD20)") (class "Default")
      (node (ref "J1") (pin "D20") (pinfunction "D20_D20") (pintype "passive+no_connect"))
    )
    (net (code "153") (name "unconnected-(J1-PadD21)") (class "Default")
      (node (ref "J1") (pin "D21") (pinfunction "D21_D21") (pintype "passive+no_connect"))
    )
    (net (code "154") (name "unconnected-(J1-PadD29)") (class "Default")
      (node (ref "J1") (pin "D29") (pinfunction "D29_D29") (pintype "passive+no_connect"))
    )
    (net (code "155") (name "unconnected-(J1-PadD30)") (class "Default")
      (node (ref "J1") (pin "D30") (pinfunction "D30_D30") (pintype "passive+no_connect"))
    )
    (net (code "156") (name "unconnected-(J1-PadD31)") (class "Default")
      (node (ref "J1") (pin "D31") (pinfunction "D31_D31") (pintype "passive+no_connect"))
    )
    (net (code "157") (name "unconnected-(J1-PadD33)") (class "Default")
      (node (ref "J1") (pin "D33") (pinfunction "D33_D33") (pintype "passive+no_connect"))
    )
    (net (code "158") (name "unconnected-(J1-PadD34)") (class "Default")
      (node (ref "J1") (pin "D34") (pinfunction "D34_D34") (pintype "passive+no_connect"))
    )
    (net (code "159") (name "unconnected-(J1-PadD35)") (class "Default")
      (node (ref "J1") (pin "D35") (pinfunction "D35_D35") (pintype "passive+no_connect"))
    )
    (net (code "160") (name "unconnected-(J1-PadE2)") (class "Default")
      (node (ref "J1") (pin "E2") (pinfunction "E2_E2") (pintype "passive+no_connect"))
    )
    (net (code "161") (name "unconnected-(J1-PadE3)") (class "Default")
      (node (ref "J1") (pin "E3") (pinfunction "E3_E3") (pintype "passive+no_connect"))
    )
    (net (code "162") (name "unconnected-(J1-PadE6)") (class "Default")
      (node (ref "J1") (pin "E6") (pinfunction "E6_E6") (pintype "passive+no_connect"))
    )
    (net (code "163") (name "unconnected-(J1-PadE7)") (class "Default")
      (node (ref "J1") (pin "E7") (pinfunction "E7_E7") (pintype "passive+no_connect"))
    )
    (net (code "164") (name "unconnected-(J1-PadE15)") (class "Default")
      (node (ref "J1") (pin "E15") (pinfunction "E15_E15") (pintype "passive+no_connect"))
    )
    (net (code "165") (name "unconnected-(J1-PadE16)") (class "Default")
      (node (ref "J1") (pin "E16") (pinfunction "E16_E16") (pintype "passive+no_connect"))
    )
    (net (code "166") (name "unconnected-(J1-PadE18)") (class "Default")
      (node (ref "J1") (pin "E18") (pinfunction "E18_E18") (pintype "passive+no_connect"))
    )
    (net (code "167") (name "unconnected-(J1-PadE19)") (class "Default")
      (node (ref "J1") (pin "E19") (pinfunction "E19_E19") (pintype "passive+no_connect"))
    )
    (net (code "168") (name "unconnected-(J1-PadE27)") (class "Default")
      (node (ref "J1") (pin "E27") (pinfunction "E27_E27") (pintype "passive+no_connect"))
    )
    (net (code "169") (name "unconnected-(J1-PadE28)") (class "Default")
      (node (ref "J1") (pin "E28") (pinfunction "E28_E28") (pintype "passive+no_connect"))
    )
    (net (code "170") (name "unconnected-(J1-PadE30)") (class "Default")
      (node (ref "J1") (pin "E30") (pinfunction "E30_E30") (pintype "passive+no_connect"))
    )
    (net (code "171") (name "unconnected-(J1-PadE31)") (class "Default")
      (node (ref "J1") (pin "E31") (pinfunction "E31_E31") (pintype "passive+no_connect"))
    )
    (net (code "172") (name "unconnected-(J1-PadE33)") (class "Default")
      (node (ref "J1") (pin "E33") (pinfunction "E33_E33") (pintype "passive+no_connect"))
    )
    (net (code "173") (name "unconnected-(J1-PadE34)") (class "Default")
      (node (ref "J1") (pin "E34") (pinfunction "E34_E34") (pintype "passive+no_connect"))
    )
    (net (code "174") (name "unconnected-(J1-PadE36)") (class "Default")
      (node (ref "J1") (pin "E36") (pinfunction "E36_E36") (pintype "passive+no_connect"))
    )
    (net (code "175") (name "unconnected-(J1-PadE37)") (class "Default")
      (node (ref "J1") (pin "E37") (pinfunction "E37_E37") (pintype "passive+no_connect"))
    )
    (net (code "176") (name "unconnected-(J1-PadF4)") (class "Default")
      (node (ref "J1") (pin "F4") (pinfunction "F4_F4") (pintype "passive+no_connect"))
    )
    (net (code "177") (name "unconnected-(J1-PadF5)") (class "Default")
      (node (ref "J1") (pin "F5") (pinfunction "F5_F5") (pintype "passive+no_connect"))
    )
    (net (code "178") (name "unconnected-(J1-PadF7)") (class "Default")
      (node (ref "J1") (pin "F7") (pinfunction "F7_F7") (pintype "passive+no_connect"))
    )
    (net (code "179") (name "unconnected-(J1-PadF8)") (class "Default")
      (node (ref "J1") (pin "F8") (pinfunction "F8_F8") (pintype "passive+no_connect"))
    )
    (net (code "180") (name "unconnected-(J1-PadF16)") (class "Default")
      (node (ref "J1") (pin "F16") (pinfunction "F16_F16") (pintype "passive+no_connect"))
    )
    (net (code "181") (name "unconnected-(J1-PadF17)") (class "Default")
      (node (ref "J1") (pin "F17") (pinfunction "F17_F17") (pintype "passive+no_connect"))
    )
    (net (code "182") (name "unconnected-(J1-PadF19)") (class "Default")
      (node (ref "J1") (pin "F19") (pinfunction "F19_F19") (pintype "passive+no_connect"))
    )
    (net (code "183") (name "unconnected-(J1-PadF20)") (class "Default")
      (node (ref "J1") (pin "F20") (pinfunction "F20_F20") (pintype "passive+no_connect"))
    )
    (net (code "184") (name "unconnected-(J1-PadF28)") (class "Default")
      (node (ref "J1") (pin "F28") (pinfunction "F28_F28") (pintype "passive+no_connect"))
    )
    (net (code "185") (name "unconnected-(J1-PadF29)") (class "Default")
      (node (ref "J1") (pin "F29") (pinfunction "F29_F29") (pintype "passive+no_connect"))
    )
    (net (code "186") (name "unconnected-(J1-PadF31)") (class "Default")
      (node (ref "J1") (pin "F31") (pinfunction "F31_F31") (pintype "passive+no_connect"))
    )
    (net (code "187") (name "unconnected-(J1-PadF32)") (class "Default")
      (node (ref "J1") (pin "F32") (pinfunction "F32_F32") (pintype "passive+no_connect"))
    )
    (net (code "188") (name "unconnected-(J1-PadF34)") (class "Default")
      (node (ref "J1") (pin "F34") (pinfunction "F34_F34") (pintype "passive+no_connect"))
    )
    (net (code "189") (name "unconnected-(J1-PadF35)") (class "Default")
      (node (ref "J1") (pin "F35") (pinfunction "F35_F35") (pintype "passive+no_connect"))
    )
    (net (code "190") (name "unconnected-(J1-PadF37)") (class "Default")
      (node (ref "J1") (pin "F37") (pinfunction "F37_F37") (pintype "passive+no_connect"))
    )
    (net (code "191") (name "unconnected-(J1-PadF38)") (class "Default")
      (node (ref "J1") (pin "F38") (pinfunction "F38_F38") (pintype "passive+no_connect"))
    )
    (net (code "192") (name "unconnected-(J1-PadG2)") (class "Default")
      (node (ref "J1") (pin "G2") (pinfunction "G2_G2") (pintype "passive+no_connect"))
    )
    (net (code "193") (name "unconnected-(J1-PadG3)") (class "Default")
      (node (ref "J1") (pin "G3") (pinfunction "G3_G3") (pintype "passive+no_connect"))
    )
    (net (code "194") (name "unconnected-(J1-PadG12)") (class "Default")
      (node (ref "J1") (pin "G12") (pinfunction "G12_G12") (pintype "passive+no_connect"))
    )
    (net (code "195") (name "unconnected-(J1-PadG13)") (class "Default")
      (node (ref "J1") (pin "G13") (pinfunction "G13_G13") (pintype "passive+no_connect"))
    )
    (net (code "196") (name "unconnected-(J1-PadG15)") (class "Default")
      (node (ref "J1") (pin "G15") (pinfunction "G15_G15") (pintype "passive+no_connect"))
    )
    (net (code "197") (name "unconnected-(J1-PadG16)") (class "Default")
      (node (ref "J1") (pin "G16") (pinfunction "G16_G16") (pintype "passive+no_connect"))
    )
    (net (code "198") (name "unconnected-(J1-PadG18)") (class "Default")
      (node (ref "J1") (pin "G18") (pinfunction "G18_G18") (pintype "passive+no_connect"))
    )
    (net (code "199") (name "unconnected-(J1-PadG19)") (class "Default")
      (node (ref "J1") (pin "G19") (pinfunction "G19_G19") (pintype "passive+no_connect"))
    )
    (net (code "200") (name "unconnected-(J1-PadG21)") (class "Default")
      (node (ref "J1") (pin "G21") (pinfunction "G21_G21") (pintype "passive+no_connect"))
    )
    (net (code "201") (name "unconnected-(J1-PadG22)") (class "Default")
      (node (ref "J1") (pin "G22") (pinfunction "G22_G22") (pintype "passive+no_connect"))
    )
    (net (code "202") (name "unconnected-(J1-PadG27)") (class "Default")
      (node (ref "J1") (pin "G27") (pinfunction "G27_G27") (pintype "passive+no_connect"))
    )
    (net (code "203") (name "unconnected-(J1-PadG28)") (class "Default")
      (node (ref "J1") (pin "G28") (pinfunction "G28_G28") (pintype "passive+no_connect"))
    )
    (net (code "204") (name "unconnected-(J1-PadG30)") (class "Default")
      (node (ref "J1") (pin "G30") (pinfunction "G30_G30") (pintype "passive+no_connect"))
    )
    (net (code "205") (name "unconnected-(J1-PadG31)") (class "Default")
      (node (ref "J1") (pin "G31") (pinfunction "G31_G31") (pintype "passive+no_connect"))
    )
    (net (code "206") (name "unconnected-(J1-PadG33)") (class "Default")
      (node (ref "J1") (pin "G33") (pinfunction "G33_G33") (pintype "passive+no_connect"))
    )
    (net (code "207") (name "unconnected-(J1-PadG34)") (class "Default")
      (node (ref "J1") (pin "G34") (pinfunction "G34_G34") (pintype "passive+no_connect"))
    )
    (net (code "208") (name "unconnected-(J1-PadG36)") (class "Default")
      (node (ref "J1") (pin "G36") (pinfunction "G36_G36") (pintype "passive+no_connect"))
    )
    (net (code "209") (name "unconnected-(J1-PadG37)") (class "Default")
      (node (ref "J1") (pin "G37") (pinfunction "G37_G37") (pintype "passive+no_connect"))
    )
    (net (code "210") (name "unconnected-(J1-PadH4)") (class "Default")
      (node (ref "J1") (pin "H4") (pinfunction "H4_H4") (pintype "passive+no_connect"))
    )
    (net (code "211") (name "unconnected-(J1-PadH5)") (class "Default")
      (node (ref "J1") (pin "H5") (pinfunction "H5_H5") (pintype "passive+no_connect"))
    )
    (net (code "212") (name "unconnected-(J1-PadH7)") (class "Default")
      (node (ref "J1") (pin "H7") (pinfunction "H7_H7") (pintype "passive+no_connect"))
    )
    (net (code "213") (name "unconnected-(J1-PadH8)") (class "Default")
      (node (ref "J1") (pin "H8") (pinfunction "H8_H8") (pintype "passive+no_connect"))
    )
    (net (code "214") (name "unconnected-(J1-PadH10)") (class "Default")
      (node (ref "J1") (pin "H10") (pinfunction "H10_H10") (pintype "passive+no_connect"))
    )
    (net (code "215") (name "unconnected-(J1-PadH11)") (class "Default")
      (node (ref "J1") (pin "H11") (pinfunction "H11_H11") (pintype "passive+no_connect"))
    )
    (net (code "216") (name "unconnected-(J1-PadH13)") (class "Default")
      (node (ref "J1") (pin "H13") (pinfunction "H13_H13") (pintype "passive+no_connect"))
    )
    (net (code "217") (name "unconnected-(J1-PadH14)") (class "Default")
      (node (ref "J1") (pin "H14") (pinfunction "H14_H14") (pintype "passive+no_connect"))
    )
    (net (code "218") (name "unconnected-(J1-PadH16)") (class "Default")
      (node (ref "J1") (pin "H16") (pinfunction "H16_H16") (pintype "passive+no_connect"))
    )
    (net (code "219") (name "unconnected-(J1-PadH17)") (class "Default")
      (node (ref "J1") (pin "H17") (pinfunction "H17_H17") (pintype "passive+no_connect"))
    )
    (net (code "220") (name "unconnected-(J1-PadH19)") (class "Default")
      (node (ref "J1") (pin "H19") (pinfunction "H19_H19") (pintype "passive+no_connect"))
    )
    (net (code "221") (name "unconnected-(J1-PadH20)") (class "Default")
      (node (ref "J1") (pin "H20") (pinfunction "H20_H20") (pintype "passive+no_connect"))
    )
    (net (code "222") (name "unconnected-(J1-PadH22)") (class "Default")
      (node (ref "J1") (pin "H22") (pinfunction "H22_H22") (pintype "passive+no_connect"))
    )
    (net (code "223") (name "unconnected-(J1-PadH23)") (class "Default")
      (node (ref "J1") (pin "H23") (pinfunction "H23_H23") (pintype "passive+no_connect"))
    )
    (net (code "224") (name "unconnected-(J1-PadH25)") (class "Default")
      (node (ref "J1") (pin "H25") (pinfunction "H25_H25") (pintype "passive+no_connect"))
    )
    (net (code "225") (name "unconnected-(J1-PadH26)") (class "Default")
      (node (ref "J1") (pin "H26") (pinfunction "H26_H26") (pintype "passive+no_connect"))
    )
    (net (code "226") (name "unconnected-(J1-PadH28)") (class "Default")
      (node (ref "J1") (pin "H28") (pinfunction "H28_H28") (pintype "passive+no_connect"))
    )
    (net (code "227") (name "unconnected-(J1-PadH29)") (class "Default")
      (node (ref "J1") (pin "H29") (pinfunction "H29_H29") (pintype "passive+no_connect"))
    )
    (net (code "228") (name "unconnected-(J1-PadH31)") (class "Default")
      (node (ref "J1") (pin "H31") (pinfunction "H31_H31") (pintype "passive+no_connect"))
    )
    (net (code "229") (name "unconnected-(J1-PadH32)") (class "Default")
      (node (ref "J1") (pin "H32") (pinfunction "H32_H32") (pintype "passive+no_connect"))
    )
    (net (code "230") (name "unconnected-(J1-PadH34)") (class "Default")
      (node (ref "J1") (pin "H34") (pinfunction "H34_H34") (pintype "passive+no_connect"))
    )
    (net (code "231") (name "unconnected-(J1-PadH35)") (class "Default")
      (node (ref "J1") (pin "H35") (pinfunction "H35_H35") (pintype "passive+no_connect"))
    )
    (net (code "232") (name "unconnected-(J1-PadH37)") (class "Default")
      (node (ref "J1") (pin "H37") (pinfunction "H37_H37") (pintype "passive+no_connect"))
    )
    (net (code "233") (name "unconnected-(J1-PadH38)") (class "Default")
      (node (ref "J1") (pin "H38") (pinfunction "H38_H38") (pintype "passive+no_connect"))
    )
    (net (code "234") (name "unconnected-(J1-PadJ21)") (class "Default")
      (node (ref "J1") (pin "J21") (pinfunction "J21_J21") (pintype "passive+no_connect"))
    )
    (net (code "235") (name "unconnected-(J1-PadJ22)") (class "Default")
      (node (ref "J1") (pin "J22") (pinfunction "J22_J22") (pintype "passive+no_connect"))
    )
    (net (code "236") (name "unconnected-(J1-PadJ36)") (class "Default")
      (node (ref "J1") (pin "J36") (pinfunction "J36_J36") (pintype "passive+no_connect"))
    )
    (net (code "237") (name "unconnected-(J1-PadJ37)") (class "Default")
      (node (ref "J1") (pin "J37") (pinfunction "J37_J37") (pintype "passive+no_connect"))
    )
    (net (code "238") (name "unconnected-(J1-PadK4)") (class "Default")
      (node (ref "J1") (pin "K4") (pinfunction "K4_K4") (pintype "passive+no_connect"))
    )
    (net (code "239") (name "unconnected-(J1-PadK5)") (class "Default")
      (node (ref "J1") (pin "K5") (pinfunction "K5_K5") (pintype "passive+no_connect"))
    )
    (net (code "240") (name "unconnected-(J1-PadK19)") (class "Default")
      (node (ref "J1") (pin "K19") (pinfunction "K19_K19") (pintype "passive+no_connect"))
    )
    (net (code "241") (name "unconnected-(J1-PadK20)") (class "Default")
      (node (ref "J1") (pin "K20") (pinfunction "K20_K20") (pintype "passive+no_connect"))
    )
    (net (code "242") (name "unconnected-(J1-PadK22)") (class "Default")
      (node (ref "J1") (pin "K22") (pinfunction "K22_K22") (pintype "passive+no_connect"))
    )
    (net (code "243") (name "unconnected-(J1-PadK23)") (class "Default")
      (node (ref "J1") (pin "K23") (pinfunction "K23_K23") (pintype "passive+no_connect"))
    )
    (net (code "244") (name "unconnected-(J1-PadK38)") (class "Default")
      (node (ref "J1") (pin "K38") (pinfunction "K38_K38") (pintype "passive+no_connect"))
    )
  )
)
